# timer-breakout.net
KiCad netlist of a schematic drawn in EAGLE
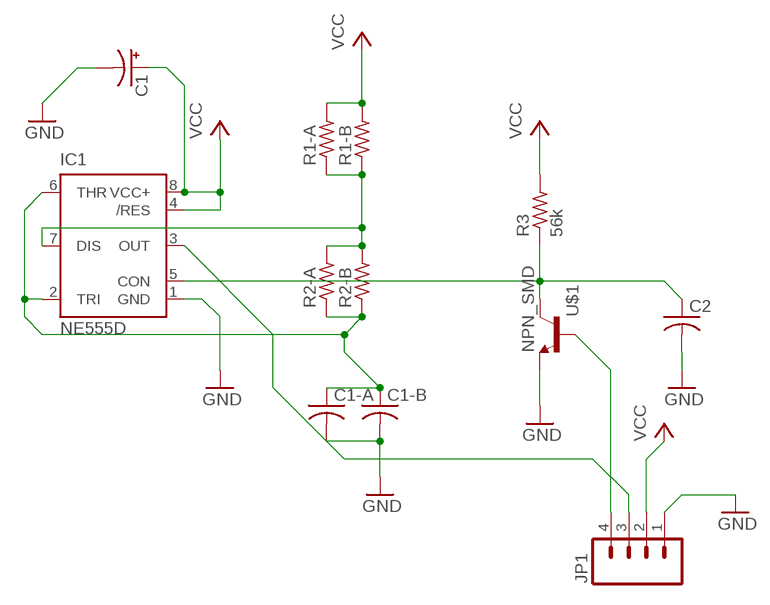
[diagram p0: schematic, sheet 1]

(export (version "E")
  (design (tool "Eeschema 10.0.6"))
  (components
    (comp (ref "C1")
      (value "CAPACITOR_POLSMCD")
      (footprint "eagle-import:SMC_D")
      (libsource (lib "eagle-import") (part "CAPACITOR_POLSMCD"))
    )
    (comp (ref "C1-A")
      (value "CAPACITORC1206K")
      (footprint "eagle-import:C1206K")
      (libsource (lib "eagle-import") (part "CAPACITORC1206K"))
    )
    (comp (ref "C1-B")
      (value "CAPACITORC0805K")
      (footprint "eagle-import:C0805K")
      (libsource (lib "eagle-import") (part "CAPACITORC0805K"))
    )
    (comp (ref "C2")
      (value "CAPACITORC1206K")
      (footprint "eagle-import:C1206K")
      (libsource (lib "eagle-import") (part "CAPACITORC1206K"))
    )
    (comp (ref "IC1")
      (value "NE555D")
      (footprint "eagle-import:SO08")
      (libsource (lib "eagle-import") (part "NE555D"))
    )
    (comp (ref "JP1")
      (value "M04PTH")
      (footprint "eagle-import:1X04")
      (libsource (lib "eagle-import") (part "M04PTH"))
    )
    (comp (ref "R1-A")
      (value "RESISTORR1206")
      (footprint "eagle-import:R1206")
      (libsource (lib "eagle-import") (part "RESISTORR1206"))
    )
    (comp (ref "R1-B")
      (value "RESISTORR0805")
      (footprint "eagle-import:R0805")
      (libsource (lib "eagle-import") (part "RESISTORR0805"))
    )
    (comp (ref "R2-A")
      (value "RESISTORR1206")
      (footprint "eagle-import:R1206")
      (libsource (lib "eagle-import") (part "RESISTORR1206"))
    )
    (comp (ref "R2-B")
      (value "RESISTORR0805")
      (footprint "eagle-import:R0805")
      (libsource (lib "eagle-import") (part "RESISTORR0805"))
    )
    (comp (ref "R3")
      (value "56k")
      (footprint "eagle-import:R0805")
      (libsource (lib "eagle-import") (part "RESISTORR0805"))
    )
    (comp (ref "U$1")
      (value "NPN_SMD")
      (footprint "eagle-import:SOT-23")
      (libsource (lib "eagle-import") (part "NPN_SMD"))
    )
  )
  (nets
    (net (code "1") (name "GND") (class "Default")
      (node (ref "C1") (pin "-") (pinfunction "-_-") (pintype "passive"))
      (node (ref "C1-A") (pin "2") (pinfunction "2_2") (pintype "passive"))
      (node (ref "C1-B") (pin "2") (pinfunction "2_2") (pintype "passive"))
      (node (ref "C2") (pin "2") (pinfunction "2_2") (pintype "passive"))
      (node (ref "IC1") (pin "1") (pinfunction "GND_1") (pintype "power_in"))
      (node (ref "JP1") (pin "1") (pinfunction "1_1") (pintype "passive"))
      (node (ref "U$1") (pin "2") (pinfunction "E_2") (pintype "passive"))
    )
    (net (code "2") (name "Net-(IC1-CON)") (class "Default")
      (node (ref "C2") (pin "1") (pinfunction "1_1") (pintype "passive"))
      (node (ref "IC1") (pin "5") (pinfunction "CON_5") (pintype "input"))
      (node (ref "R3") (pin "1") (pinfunction "1_1") (pintype "passive"))
      (node (ref "U$1") (pin "3") (pinfunction "C_3") (pintype "passive"))
    )
    (net (code "3") (name "Net-(IC1-DIS)") (class "Default")
      (node (ref "IC1") (pin "7") (pinfunction "DIS_7") (pintype "input"))
      (node (ref "R1-A") (pin "1") (pinfunction "1_1") (pintype "passive"))
      (node (ref "R1-B") (pin "1") (pinfunction "1_1") (pintype "passive"))
      (node (ref "R2-A") (pin "2") (pinfunction "2_2") (pintype "passive"))
      (node (ref "R2-B") (pin "2") (pinfunction "2_2") (pintype "passive"))
    )
    (net (code "4") (name "Net-(IC1-OUT)") (class "Default")
      (node (ref "IC1") (pin "3") (pinfunction "OUT_3") (pintype "output"))
      (node (ref "JP1") (pin "3") (pinfunction "3_3") (pintype "passive"))
    )
    (net (code "5") (name "Net-(IC1-THR)") (class "Default")
      (node (ref "C1-A") (pin "1") (pinfunction "1_1") (pintype "passive"))
      (node (ref "C1-B") (pin "1") (pinfunction "1_1") (pintype "passive"))
      (node (ref "IC1") (pin "2") (pinfunction "TRI_2") (pintype "input"))
      (node (ref "IC1") (pin "6") (pinfunction "THR_6") (pintype "input"))
      (node (ref "R2-A") (pin "1") (pinfunction "1_1") (pintype "passive"))
      (node (ref "R2-B") (pin "1") (pinfunction "1_1") (pintype "passive"))
    )
    (net (code "6") (name "Net-(U$1-B)") (class "Default")
      (node (ref "JP1") (pin "4") (pinfunction "4_4") (pintype "passive"))
      (node (ref "U$1") (pin "1") (pinfunction "B_1") (pintype "passive"))
    )
    (net (code "7") (name "VCC") (class "Default")
      (node (ref "C1") (pin "+") (pinfunction "+_+") (pintype "passive"))
      (node (ref "IC1") (pin "4") (pinfunction "/RES_4") (pintype "input"))
      (node (ref "IC1") (pin "8") (pinfunction "VCC+_8") (pintype "power_in"))
      (node (ref "JP1") (pin "2") (pinfunction "2_2") (pintype "passive"))
      (node (ref "R1-A") (pin "2") (pinfunction "2_2") (pintype "passive"))
      (node (ref "R1-B") (pin "2") (pinfunction "2_2") (pintype "passive"))
      (node (ref "R3") (pin "2") (pinfunction "2_2") (pintype "passive"))
    )
  )
)
